# SCH_Electric-Kiln-Controller_EasyEDA.net
KiCad netlist of a schematic drawn in EasyEDA
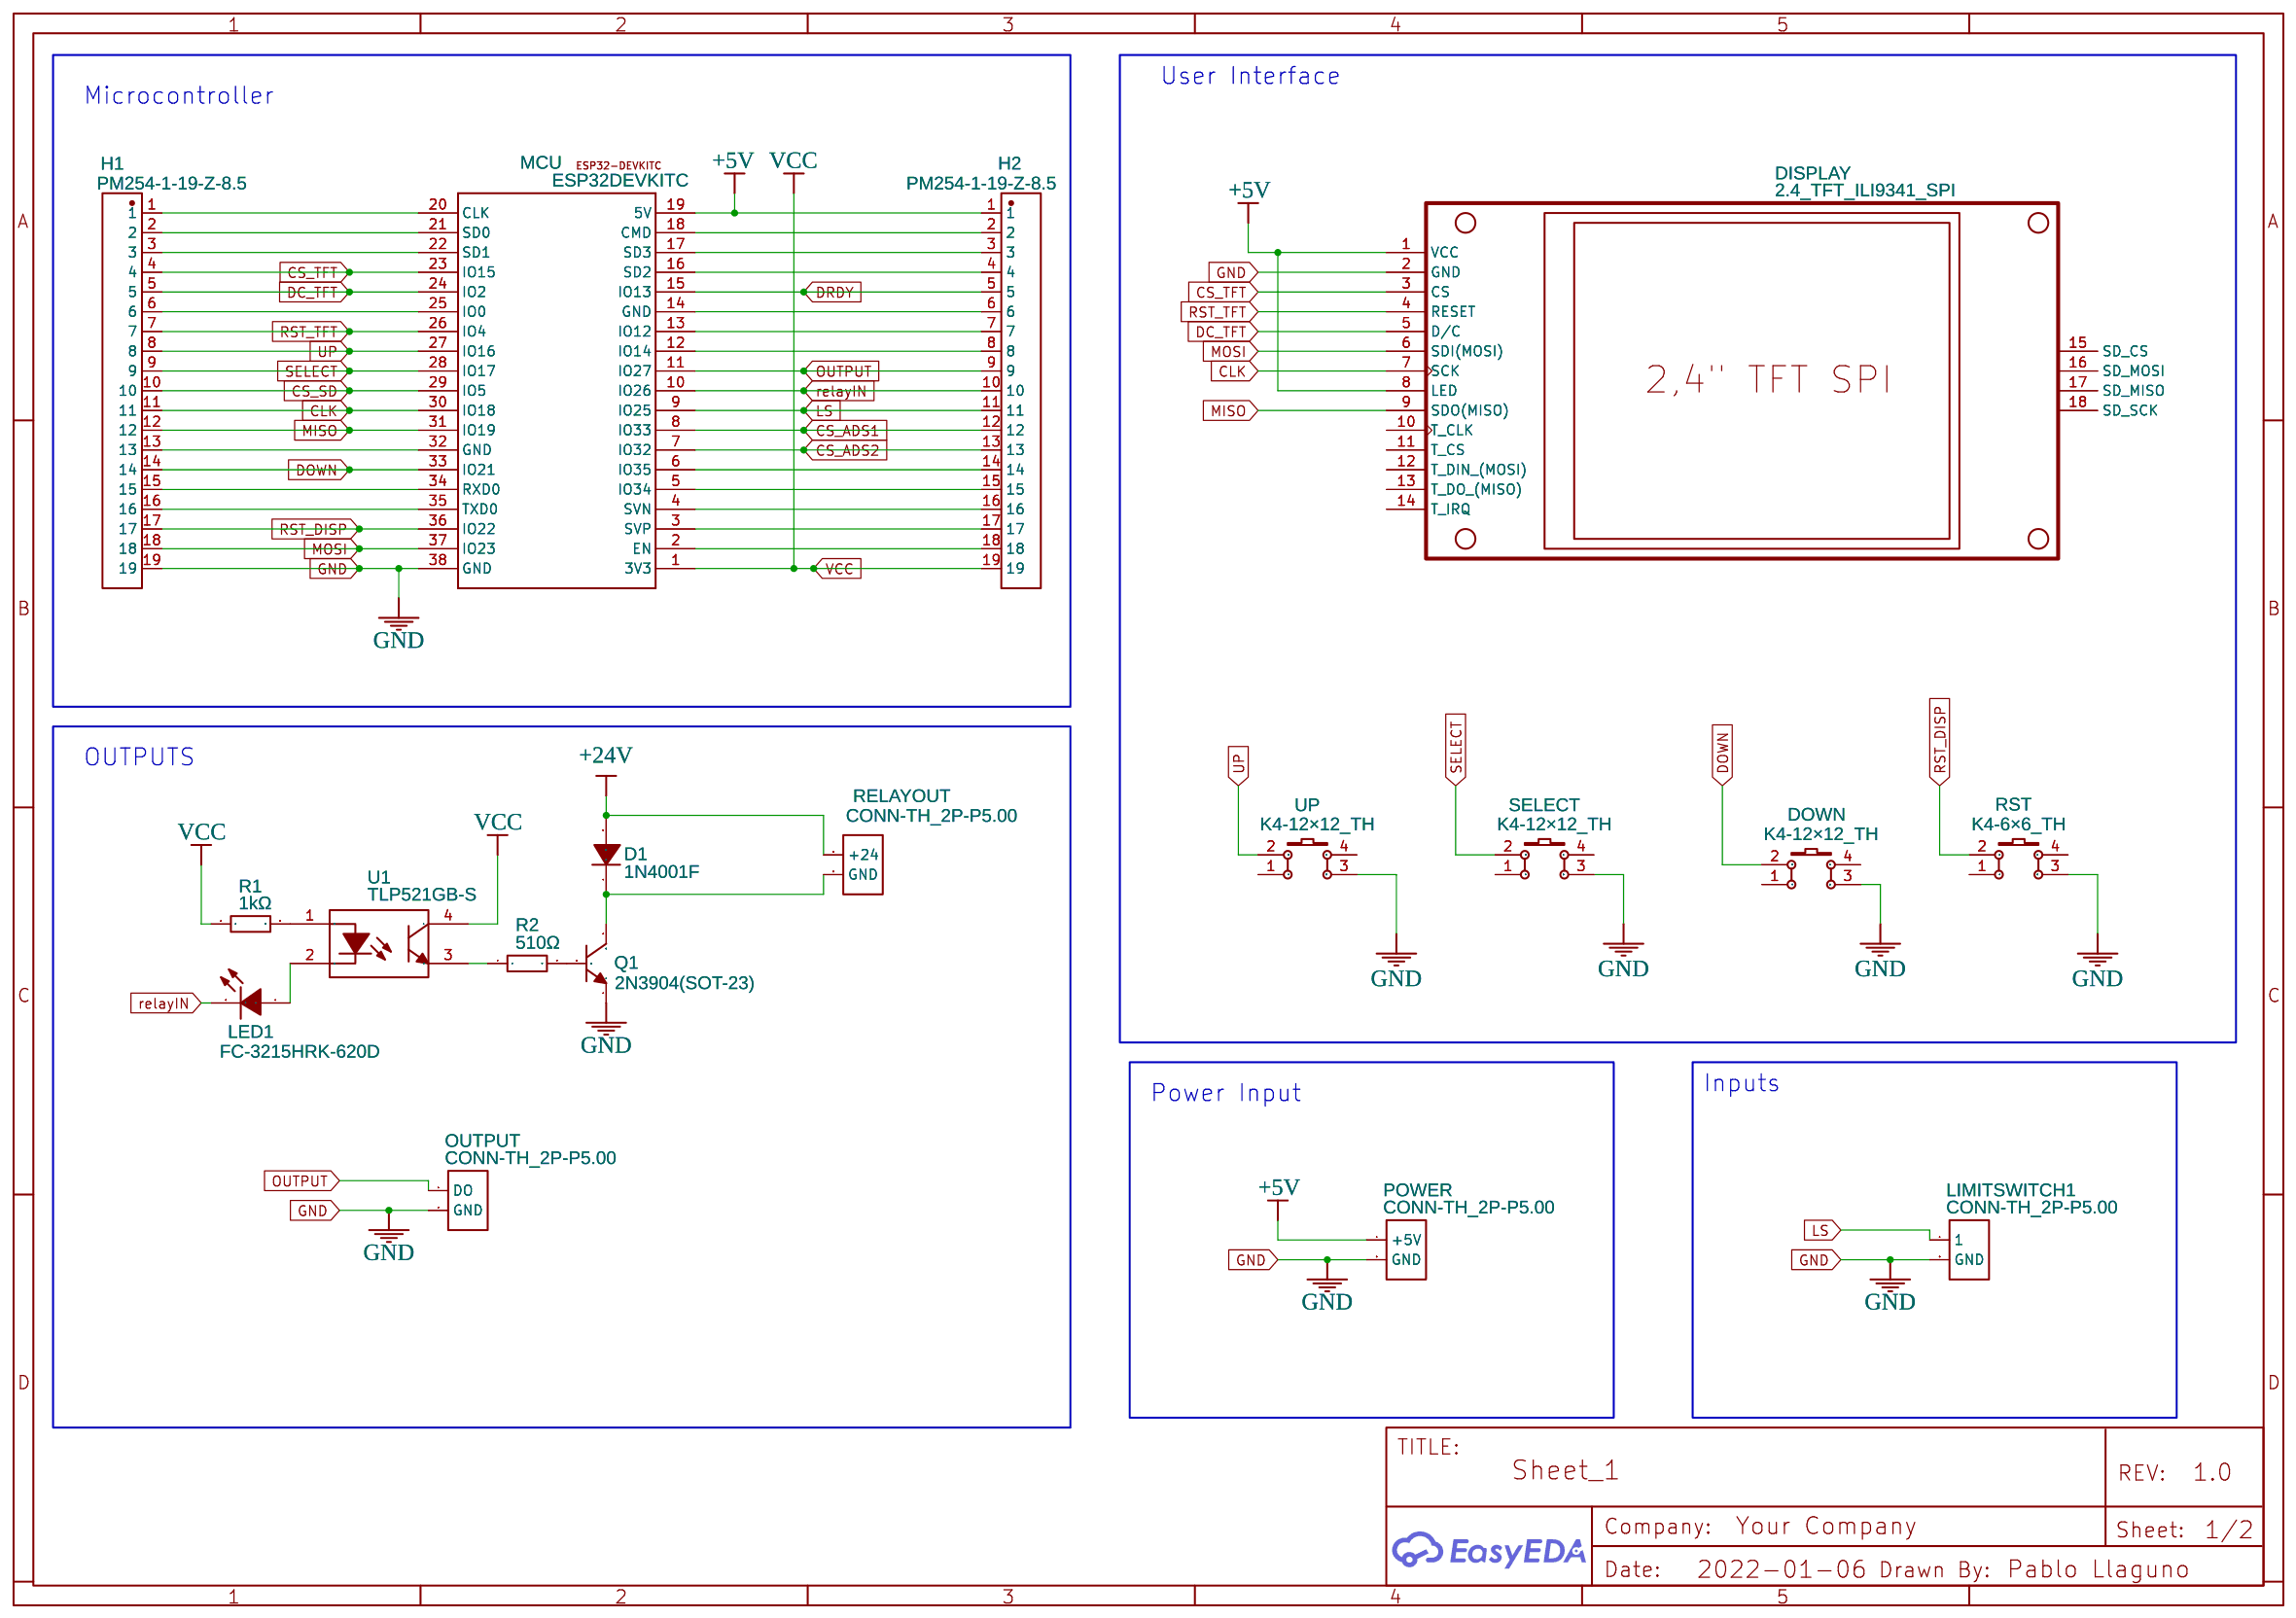
[diagram p0: Sheet_1]
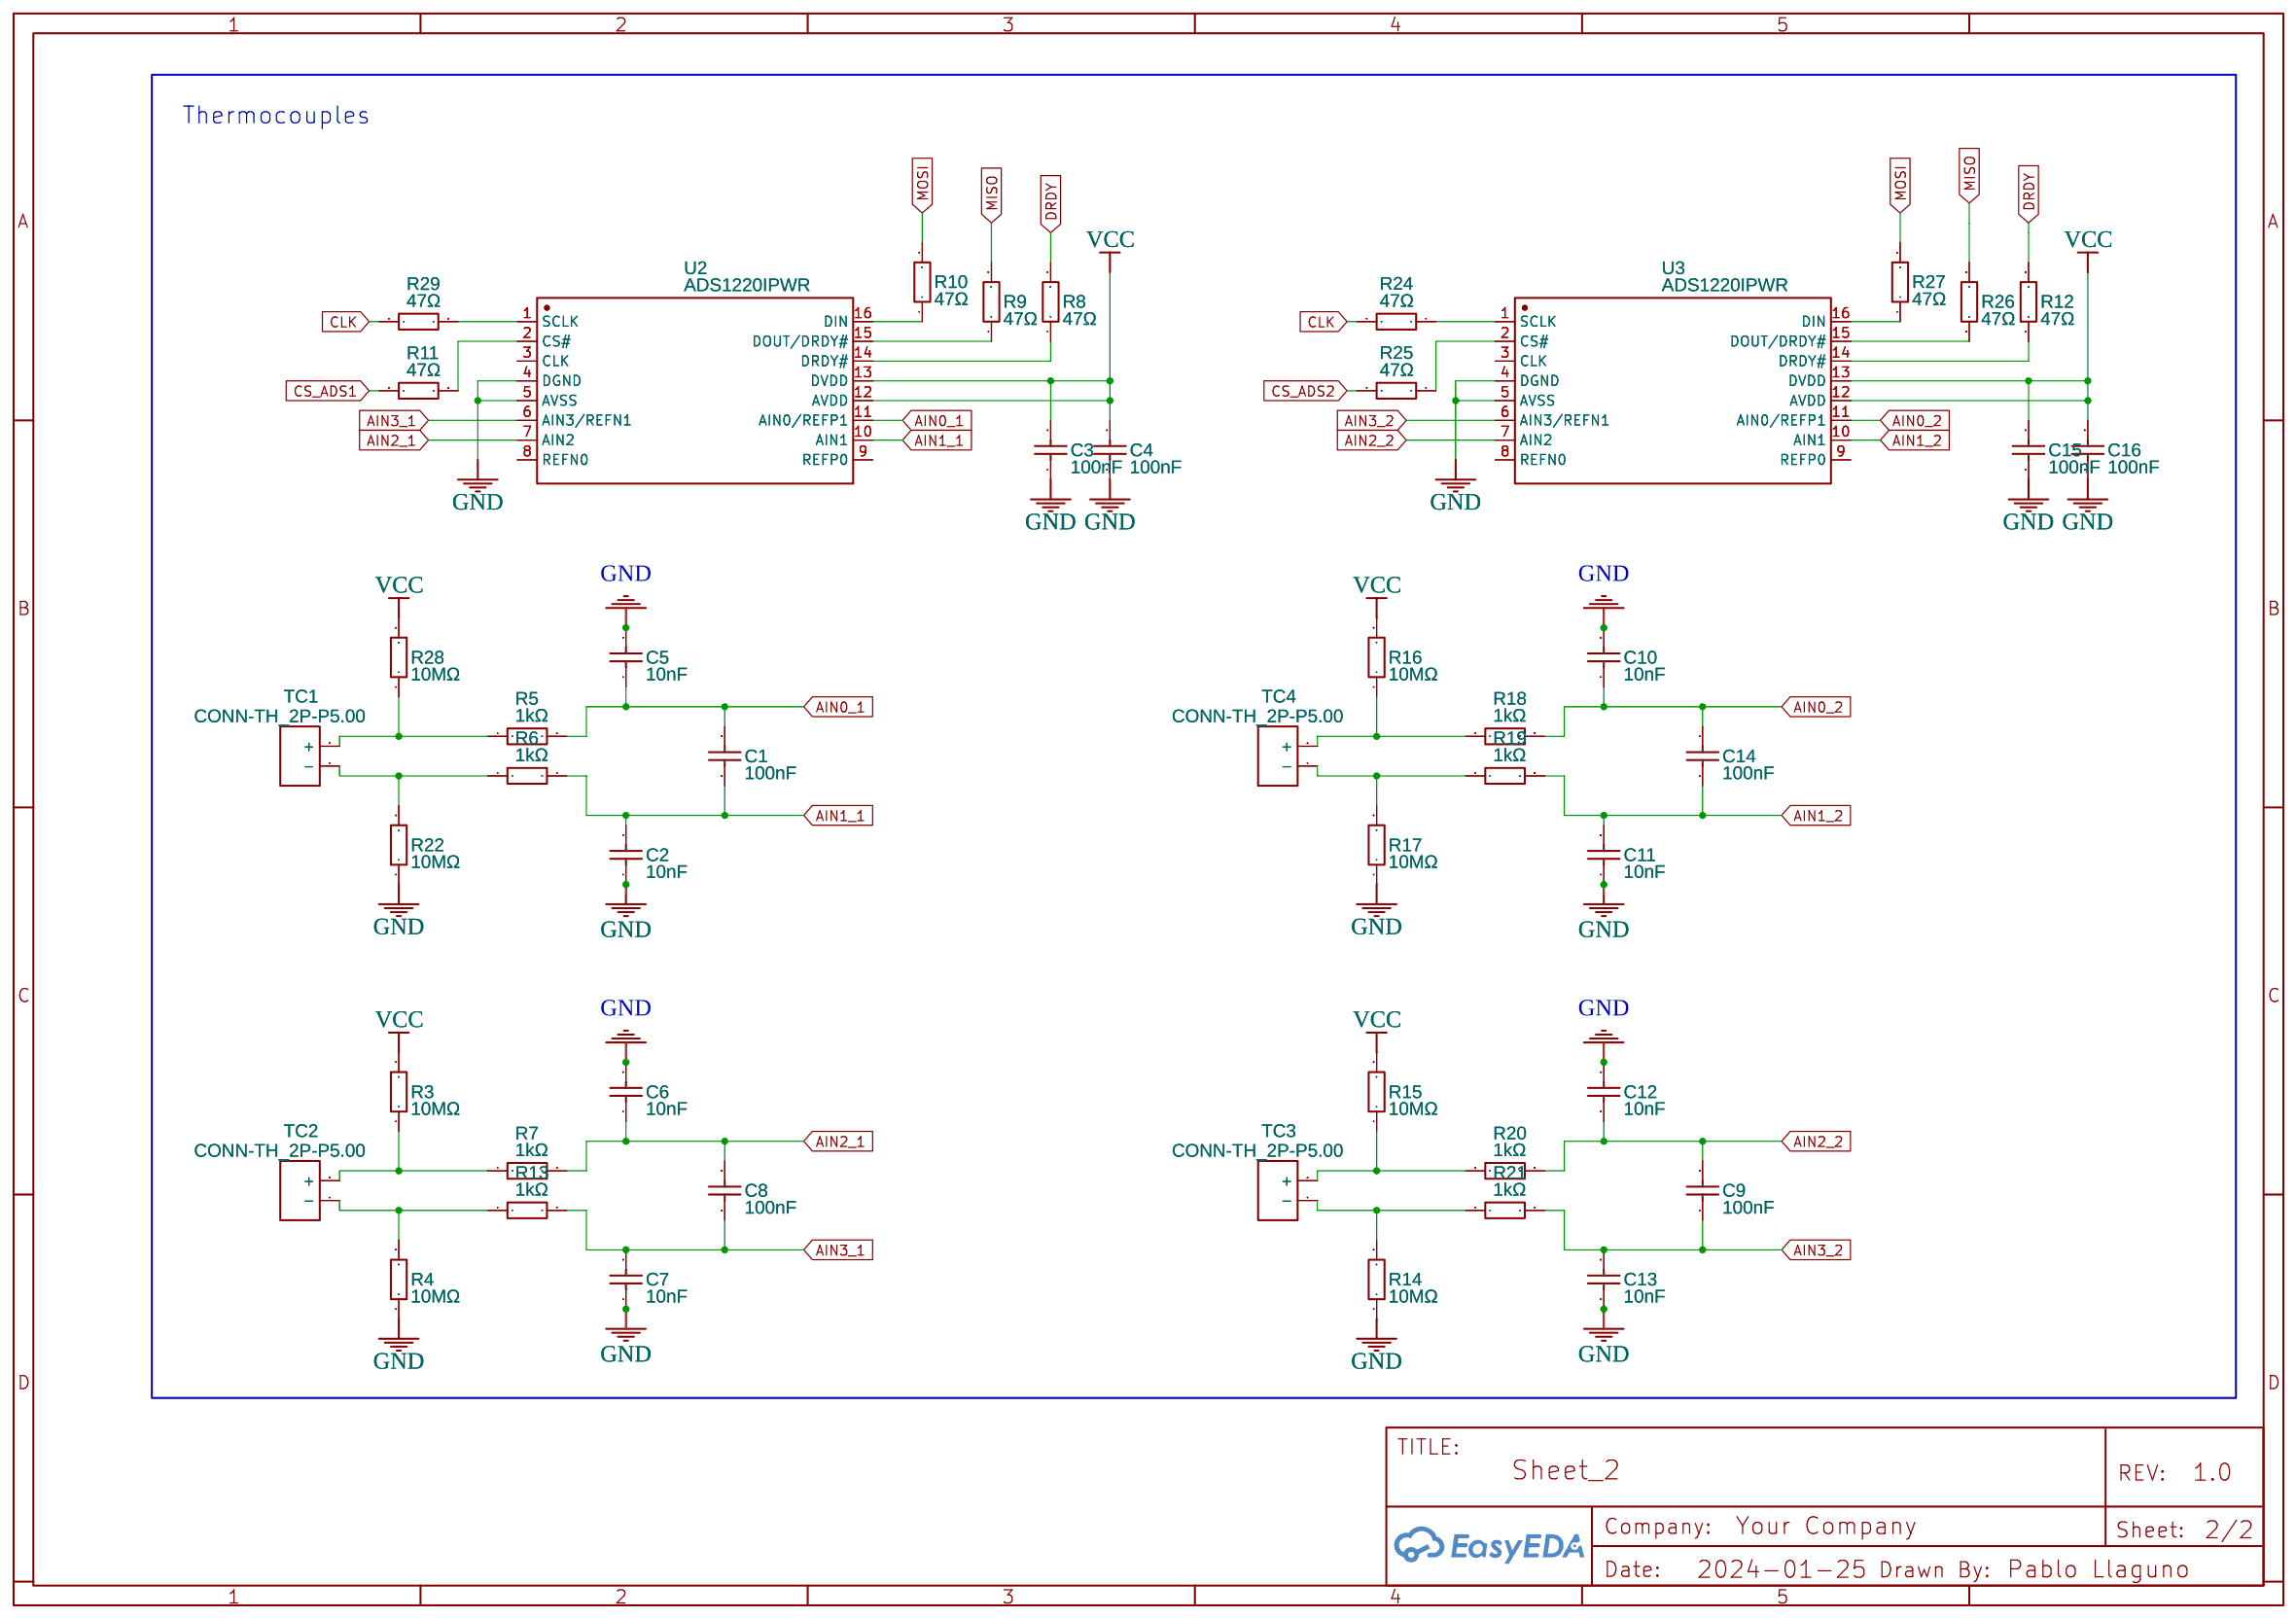
[diagram p1: Sheet_2]

(export (version "E")
  (design (tool "Eeschema 10.0.6"))
  (components
    (comp (ref "D1")
      (value "1N4001F")
      (fields (field (name "Manufacturer") "SHIKUES(时科)"))
      (libsource (lib "") (part "1N4001F"))
    )
    (comp (ref "DISPLAY") (value "2.4_TFT_ILI9341_SPI") (libsource (lib "") (part "2.4_TFT_ILI9341_SPI")))
    (comp (ref "DOWN")
      (value "K4-12×12_TH")
      (fields (field (name "Manufacturer Part") "K2-1103DP-M4SW-04") (field (name "Manufacturer") "韩国韩荣"))
      (libsource (lib "") (part "K4-12×12_TH"))
    )
    (comp (ref "H1")
      (value "PM254-1-19-Z-8.5")
      (fields (field (name "Manufacturer") "HCTL(华灿天禄)"))
      (libsource (lib "") (part "PM254-1-19-Z-8.5_1"))
    )
    (comp (ref "H2")
      (value "PM254-1-19-Z-8.5")
      (fields (field (name "Manufacturer") "HCTL(华灿天禄)"))
      (libsource (lib "") (part "PM254-1-19-Z-8.5"))
    )
    (comp (ref "LED1")
      (value "FC-3215HRK-620D")
      (fields (field (name "Manufacturer Part") "NCD1206R1") (field (name "Manufacturer") "国星光电"))
      (libsource (lib "") (part "FC-3215HRK-620D"))
    )
    (comp (ref "LIMITSWITCH1") (value "CONN-TH_2P-P5.00") (libsource (lib "") (part "CONN-TH_2P-P5.00_2")))
    (comp (ref "MCU") (value "ESP32DEVKITC") (libsource (lib "") (part "ESP32DEVKITC")))
    (comp (ref "OUTPUT") (value "CONN-TH_2P-P5.00") (libsource (lib "") (part "CONN-TH_2P-P5.00_1")))
    (comp (ref "POWER") (value "CONN-TH_2P-P5.00") (libsource (lib "") (part "CONN-TH_2P-P5.00")))
    (comp (ref "Q1")
      (value "2N3904(SOT-23)")
      (fields (field (name "Manufacturer Part") "2n3904S-RTK/PS") (field (name "Manufacturer") "KEC"))
      (libsource (lib "") (part "2N3904(SOT-23)"))
    )
    (comp (ref "R1")
      (value "1kΩ")
      (fields
        (field (name "Manufacturer Part") "0603WAF1001T5E")
        (field (name "Manufacturer") "UNI-ROYAL(厚声)")
      )
      (libsource (lib "") (part "0603WAF1001T5E"))
    )
    (comp (ref "R2")
      (value "510Ω")
      (fields
        (field (name "Manufacturer Part") "0603WAF5100T5E")
        (field (name "Manufacturer") "UNI-ROYAL(厚声)")
      )
      (libsource (lib "") (part "0603WAF5100T5E"))
    )
    (comp (ref "RELAYOUT") (value "CONN-TH_2P-P5.00") (libsource (lib "") (part "CONN-TH_2P-P5.00_3")))
    (comp (ref "RST")
      (value "K4-6×6_TH")
      (fields (field (name "Manufacturer Part") "K2-1102DP-E4SW-04") (field (name "Manufacturer") "韩国韩荣"))
      (libsource (lib "") (part "K4-6×6_TH"))
    )
    (comp (ref "SELECT")
      (value "K4-12×12_TH")
      (fields (field (name "Manufacturer Part") "K2-1103DP-M4SW-04") (field (name "Manufacturer") "韩国韩荣"))
      (libsource (lib "") (part "K4-12×12_TH_1"))
    )
    (comp (ref "U1")
      (value "TLP521GB-S")
      (fields (field (name "Manufacturer") "UMW(广东友台半导体)"))
      (libsource (lib "") (part "TLP521GB-S"))
    )
    (comp (ref "UP")
      (value "K4-12×12_TH")
      (fields (field (name "Manufacturer Part") "K2-1103DP-M4SW-04") (field (name "Manufacturer") "韩国韩荣"))
      (libsource (lib "") (part "K4-12×12_TH_2"))
    )
    (comp (ref "C1")
      (value "100nF")
      (fields
        (field (name "Manufacturer Part") "CL21B104KCFNNNE")
        (field (name "Manufacturer") "SAMSUNG(三星)")
      )
      (libsource (lib "") (part "CL21B104KCFNNNE"))
    )
    (comp (ref "C2")
      (value "10nF")
      (fields
        (field (name "Manufacturer Part") "CL21B103KBANNNC")
        (field (name "Manufacturer") "SAMSUNG(三星)")
      )
      (libsource (lib "") (part "CL21B103KBANNNC"))
    )
    (comp (ref "C3")
      (value "100nF")
      (fields
        (field (name "Manufacturer Part") "CL21B104KCFNNNE")
        (field (name "Manufacturer") "SAMSUNG(三星)")
      )
      (libsource (lib "") (part "CL21B104KCFNNNE"))
    )
    (comp (ref "C4")
      (value "100nF")
      (fields
        (field (name "Manufacturer Part") "CL21B104KCFNNNE")
        (field (name "Manufacturer") "SAMSUNG(三星)")
      )
      (libsource (lib "") (part "CL21B104KCFNNNE"))
    )
    (comp (ref "C5")
      (value "10nF")
      (fields
        (field (name "Manufacturer Part") "CL21B103KBANNNC")
        (field (name "Manufacturer") "SAMSUNG(三星)")
      )
      (libsource (lib "") (part "CL21B103KBANNNC"))
    )
    (comp (ref "C6")
      (value "10nF")
      (fields
        (field (name "Manufacturer Part") "CL21B103KBANNNC")
        (field (name "Manufacturer") "SAMSUNG(三星)")
      )
      (libsource (lib "") (part "CL21B103KBANNNC"))
    )
    (comp (ref "C7")
      (value "10nF")
      (fields
        (field (name "Manufacturer Part") "CL21B103KBANNNC")
        (field (name "Manufacturer") "SAMSUNG(三星)")
      )
      (libsource (lib "") (part "CL21B103KBANNNC"))
    )
    (comp (ref "C8")
      (value "100nF")
      (fields
        (field (name "Manufacturer Part") "CL21B104KCFNNNE")
        (field (name "Manufacturer") "SAMSUNG(三星)")
      )
      (libsource (lib "") (part "CL21B104KCFNNNE"))
    )
    (comp (ref "C9")
      (value "100nF")
      (fields
        (field (name "Manufacturer Part") "CL21B104KCFNNNE")
        (field (name "Manufacturer") "SAMSUNG(三星)")
      )
      (libsource (lib "") (part "CL21B104KCFNNNE"))
    )
    (comp (ref "C10")
      (value "10nF")
      (fields
        (field (name "Manufacturer Part") "CL21B103KBANNNC")
        (field (name "Manufacturer") "SAMSUNG(三星)")
      )
      (libsource (lib "") (part "CL21B103KBANNNC"))
    )
    (comp (ref "C11")
      (value "10nF")
      (fields
        (field (name "Manufacturer Part") "CL21B103KBANNNC")
        (field (name "Manufacturer") "SAMSUNG(三星)")
      )
      (libsource (lib "") (part "CL21B103KBANNNC"))
    )
    (comp (ref "C12")
      (value "10nF")
      (fields
        (field (name "Manufacturer Part") "CL21B103KBANNNC")
        (field (name "Manufacturer") "SAMSUNG(三星)")
      )
      (libsource (lib "") (part "CL21B103KBANNNC"))
    )
    (comp (ref "C13")
      (value "10nF")
      (fields
        (field (name "Manufacturer Part") "CL21B103KBANNNC")
        (field (name "Manufacturer") "SAMSUNG(三星)")
      )
      (libsource (lib "") (part "CL21B103KBANNNC"))
    )
    (comp (ref "C14")
      (value "100nF")
      (fields
        (field (name "Manufacturer Part") "CL21B104KCFNNNE")
        (field (name "Manufacturer") "SAMSUNG(三星)")
      )
      (libsource (lib "") (part "CL21B104KCFNNNE"))
    )
    (comp (ref "C15")
      (value "100nF")
      (fields
        (field (name "Manufacturer Part") "CL21B104KCFNNNE")
        (field (name "Manufacturer") "SAMSUNG(三星)")
      )
      (libsource (lib "") (part "CL21B104KCFNNNE"))
    )
    (comp (ref "C16")
      (value "100nF")
      (fields
        (field (name "Manufacturer Part") "CL21B104KCFNNNE")
        (field (name "Manufacturer") "SAMSUNG(三星)")
      )
      (libsource (lib "") (part "CL21B104KCFNNNE"))
    )
    (comp (ref "R3")
      (value "10MΩ")
      (fields
        (field (name "Manufacturer Part") "0603WAJ0106T5E")
        (field (name "Manufacturer") "UNI-ROYAL(厚声)")
      )
      (libsource (lib "") (part "0603WAJ0106T5E"))
    )
    (comp (ref "R4")
      (value "10MΩ")
      (fields
        (field (name "Manufacturer Part") "0603WAJ0106T5E")
        (field (name "Manufacturer") "UNI-ROYAL(厚声)")
      )
      (libsource (lib "") (part "0603WAJ0106T5E"))
    )
    (comp (ref "R5")
      (value "1kΩ")
      (fields
        (field (name "Manufacturer Part") "0603WAF1001T5E")
        (field (name "Manufacturer") "UNI-ROYAL(厚声)")
      )
      (libsource (lib "") (part "0603WAF1001T5E"))
    )
    (comp (ref "R6")
      (value "1kΩ")
      (fields
        (field (name "Manufacturer Part") "0603WAF1001T5E")
        (field (name "Manufacturer") "UNI-ROYAL(厚声)")
      )
      (libsource (lib "") (part "0603WAF1001T5E"))
    )
    (comp (ref "R7")
      (value "1kΩ")
      (fields
        (field (name "Manufacturer Part") "0603WAF1001T5E")
        (field (name "Manufacturer") "UNI-ROYAL(厚声)")
      )
      (libsource (lib "") (part "0603WAF1001T5E"))
    )
    (comp (ref "R8")
      (value "47Ω")
      (fields
        (field (name "Manufacturer Part") "0603WAJ0470T5E")
        (field (name "Manufacturer") "UNI-ROYAL(厚声)")
      )
      (libsource (lib "") (part "0603WAJ0470T5E_2"))
    )
    (comp (ref "R9")
      (value "47Ω")
      (fields
        (field (name "Manufacturer Part") "0603WAJ0470T5E")
        (field (name "Manufacturer") "UNI-ROYAL(厚声)")
      )
      (libsource (lib "") (part "0603WAJ0470T5E_2"))
    )
    (comp (ref "R10")
      (value "47Ω")
      (fields
        (field (name "Manufacturer Part") "0603WAJ0470T5E")
        (field (name "Manufacturer") "UNI-ROYAL(厚声)")
      )
      (libsource (lib "") (part "0603WAJ0470T5E_2"))
    )
    (comp (ref "R11")
      (value "47Ω")
      (fields
        (field (name "Manufacturer Part") "0603WAJ0470T5E")
        (field (name "Manufacturer") "UNI-ROYAL(厚声)")
      )
      (libsource (lib "") (part "0603WAJ0470T5E"))
    )
    (comp (ref "R12")
      (value "47Ω")
      (fields
        (field (name "Manufacturer Part") "0603WAJ0470T5E")
        (field (name "Manufacturer") "UNI-ROYAL(厚声)")
      )
      (libsource (lib "") (part "0603WAJ0470T5E_2"))
    )
    (comp (ref "R13")
      (value "1kΩ")
      (fields
        (field (name "Manufacturer Part") "0603WAF1001T5E")
        (field (name "Manufacturer") "UNI-ROYAL(厚声)")
      )
      (libsource (lib "") (part "0603WAF1001T5E"))
    )
    (comp (ref "R14")
      (value "10MΩ")
      (fields
        (field (name "Manufacturer Part") "0603WAJ0106T5E")
        (field (name "Manufacturer") "UNI-ROYAL(厚声)")
      )
      (libsource (lib "") (part "0603WAJ0106T5E"))
    )
    (comp (ref "R15")
      (value "10MΩ")
      (fields
        (field (name "Manufacturer Part") "0603WAJ0106T5E")
        (field (name "Manufacturer") "UNI-ROYAL(厚声)")
      )
      (libsource (lib "") (part "0603WAJ0106T5E"))
    )
    (comp (ref "R16")
      (value "10MΩ")
      (fields
        (field (name "Manufacturer Part") "0603WAJ0106T5E")
        (field (name "Manufacturer") "UNI-ROYAL(厚声)")
      )
      (libsource (lib "") (part "0603WAJ0106T5E"))
    )
    (comp (ref "R17")
      (value "10MΩ")
      (fields
        (field (name "Manufacturer Part") "0603WAJ0106T5E")
        (field (name "Manufacturer") "UNI-ROYAL(厚声)")
      )
      (libsource (lib "") (part "0603WAJ0106T5E"))
    )
    (comp (ref "R18")
      (value "1kΩ")
      (fields
        (field (name "Manufacturer Part") "0603WAF1001T5E")
        (field (name "Manufacturer") "UNI-ROYAL(厚声)")
      )
      (libsource (lib "") (part "0603WAF1001T5E"))
    )
    (comp (ref "R19")
      (value "1kΩ")
      (fields
        (field (name "Manufacturer Part") "0603WAF1001T5E")
        (field (name "Manufacturer") "UNI-ROYAL(厚声)")
      )
      (libsource (lib "") (part "0603WAF1001T5E"))
    )
    (comp (ref "R20")
      (value "1kΩ")
      (fields
        (field (name "Manufacturer Part") "0603WAF1001T5E")
        (field (name "Manufacturer") "UNI-ROYAL(厚声)")
      )
      (libsource (lib "") (part "0603WAF1001T5E"))
    )
    (comp (ref "R21")
      (value "1kΩ")
      (fields
        (field (name "Manufacturer Part") "0603WAF1001T5E")
        (field (name "Manufacturer") "UNI-ROYAL(厚声)")
      )
      (libsource (lib "") (part "0603WAF1001T5E"))
    )
    (comp (ref "R22")
      (value "10MΩ")
      (fields
        (field (name "Manufacturer Part") "0603WAJ0106T5E")
        (field (name "Manufacturer") "UNI-ROYAL(厚声)")
      )
      (libsource (lib "") (part "0603WAJ0106T5E"))
    )
    (comp (ref "R24")
      (value "47Ω")
      (fields
        (field (name "Manufacturer Part") "0603WAJ0470T5E")
        (field (name "Manufacturer") "UNI-ROYAL(厚声)")
      )
      (libsource (lib "") (part "0603WAJ0470T5E_1"))
    )
    (comp (ref "R25")
      (value "47Ω")
      (fields
        (field (name "Manufacturer Part") "0603WAJ0470T5E")
        (field (name "Manufacturer") "UNI-ROYAL(厚声)")
      )
      (libsource (lib "") (part "0603WAJ0470T5E_1"))
    )
    (comp (ref "R26")
      (value "47Ω")
      (fields
        (field (name "Manufacturer Part") "0603WAJ0470T5E")
        (field (name "Manufacturer") "UNI-ROYAL(厚声)")
      )
      (libsource (lib "") (part "0603WAJ0470T5E_2"))
    )
    (comp (ref "R27")
      (value "47Ω")
      (fields
        (field (name "Manufacturer Part") "0603WAJ0470T5E")
        (field (name "Manufacturer") "UNI-ROYAL(厚声)")
      )
      (libsource (lib "") (part "0603WAJ0470T5E_2"))
    )
    (comp (ref "R28")
      (value "10MΩ")
      (fields
        (field (name "Manufacturer Part") "0603WAJ0106T5E")
        (field (name "Manufacturer") "UNI-ROYAL(厚声)")
      )
      (libsource (lib "") (part "0603WAJ0106T5E"))
    )
    (comp (ref "R29")
      (value "47Ω")
      (fields
        (field (name "Manufacturer Part") "0603WAJ0470T5E")
        (field (name "Manufacturer") "UNI-ROYAL(厚声)")
      )
      (libsource (lib "") (part "0603WAJ0470T5E"))
    )
    (comp (ref "TC1") (value "CONN-TH_2P-P5.00") (libsource (lib "") (part "CONN-TH_2P-P5.00")))
    (comp (ref "TC2") (value "CONN-TH_2P-P5.00") (libsource (lib "") (part "CONN-TH_2P-P5.00")))
    (comp (ref "TC3") (value "CONN-TH_2P-P5.00") (libsource (lib "") (part "CONN-TH_2P-P5.00")))
    (comp (ref "TC4") (value "CONN-TH_2P-P5.00") (libsource (lib "") (part "CONN-TH_2P-P5.00")))
    (comp (ref "U2")
      (value "ADS1220IPWR")
      (fields (field (name "Manufacturer") "TI(德州仪器)"))
      (libsource (lib "") (part "ADS1220IPWR"))
    )
    (comp (ref "U3")
      (value "ADS1220IPWR")
      (fields (field (name "Manufacturer") "TI(德州仪器)"))
      (libsource (lib "") (part "ADS1220IPWR"))
    )
  )
  (nets
    (net (code "1") (name "+5V") (class "Default")
      (node (ref "DISPLAY") (pin "1") (pinfunction "VCC_1") (pintype "passive"))
      (node (ref "DISPLAY") (pin "8") (pinfunction "LED_8") (pintype "passive"))
      (node (ref "H2") (pin "1") (pinfunction "1_1") (pintype "unspecified"))
      (node (ref "MCU") (pin "19") (pinfunction "5V_19") (pintype "bidirectional"))
      (node (ref "POWER") (pin "1") (pinfunction "+5V_1") (pintype "unspecified"))
    )
    (net (code "2") (name "+24V") (class "Default")
      (node (ref "D1") (pin "2") (pinfunction "A_2") (pintype "unspecified"))
      (node (ref "RELAYOUT") (pin "1") (pinfunction "+24_1") (pintype "unspecified"))
    )
    (net (code "3") (name "AIN0_1") (class "Default")
      (node (ref "C1") (pin "2") (pinfunction "2_2") (pintype "input"))
      (node (ref "C5") (pin "1") (pinfunction "1_1") (pintype "input"))
      (node (ref "R5") (pin "2") (pinfunction "2_2") (pintype "input"))
      (node (ref "U2") (pin "11") (pinfunction "AIN0/REFP1_11") (pintype "unspecified"))
    )
    (net (code "4") (name "AIN0_2") (class "Default")
      (node (ref "C10") (pin "1") (pinfunction "1_1") (pintype "input"))
      (node (ref "C14") (pin "2") (pinfunction "2_2") (pintype "input"))
      (node (ref "R18") (pin "2") (pinfunction "2_2") (pintype "input"))
      (node (ref "U3") (pin "11") (pinfunction "AIN0/REFP1_11") (pintype "unspecified"))
    )
    (net (code "5") (name "AIN1_1") (class "Default")
      (node (ref "C1") (pin "1") (pinfunction "1_1") (pintype "input"))
      (node (ref "C2") (pin "2") (pinfunction "2_2") (pintype "input"))
      (node (ref "R6") (pin "2") (pinfunction "2_2") (pintype "input"))
      (node (ref "U2") (pin "10") (pinfunction "AIN1_10") (pintype "unspecified"))
    )
    (net (code "6") (name "AIN1_2") (class "Default")
      (node (ref "C11") (pin "2") (pinfunction "2_2") (pintype "input"))
      (node (ref "C14") (pin "1") (pinfunction "1_1") (pintype "input"))
      (node (ref "R19") (pin "2") (pinfunction "2_2") (pintype "input"))
      (node (ref "U3") (pin "10") (pinfunction "AIN1_10") (pintype "unspecified"))
    )
    (net (code "7") (name "AIN2_1") (class "Default")
      (node (ref "C6") (pin "1") (pinfunction "1_1") (pintype "input"))
      (node (ref "C8") (pin "2") (pinfunction "2_2") (pintype "input"))
      (node (ref "R7") (pin "2") (pinfunction "2_2") (pintype "input"))
      (node (ref "U2") (pin "7") (pinfunction "AIN2_7") (pintype "unspecified"))
    )
    (net (code "8") (name "AIN2_2") (class "Default")
      (node (ref "C12") (pin "1") (pinfunction "1_1") (pintype "input"))
      (node (ref "C9") (pin "2") (pinfunction "2_2") (pintype "input"))
      (node (ref "R20") (pin "2") (pinfunction "2_2") (pintype "input"))
      (node (ref "U3") (pin "7") (pinfunction "AIN2_7") (pintype "unspecified"))
    )
    (net (code "9") (name "AIN3_1") (class "Default")
      (node (ref "C7") (pin "2") (pinfunction "2_2") (pintype "input"))
      (node (ref "C8") (pin "1") (pinfunction "1_1") (pintype "input"))
      (node (ref "R13") (pin "2") (pinfunction "2_2") (pintype "input"))
      (node (ref "U2") (pin "6") (pinfunction "AIN3/REFN1_6") (pintype "unspecified"))
    )
    (net (code "10") (name "AIN3_2") (class "Default")
      (node (ref "C13") (pin "2") (pinfunction "2_2") (pintype "input"))
      (node (ref "C9") (pin "1") (pinfunction "1_1") (pintype "input"))
      (node (ref "R21") (pin "2") (pinfunction "2_2") (pintype "input"))
      (node (ref "U3") (pin "6") (pinfunction "AIN3/REFN1_6") (pintype "unspecified"))
    )
    (net (code "11") (name "CLK") (class "Default")
      (node (ref "DISPLAY") (pin "7") (pinfunction "SCK_7") (pintype "input"))
      (node (ref "H1") (pin "11") (pinfunction "11_11") (pintype "unspecified"))
      (node (ref "MCU") (pin "30") (pinfunction "IO18_30") (pintype "bidirectional"))
      (node (ref "R24") (pin "2") (pinfunction "2_2") (pintype "input"))
      (node (ref "R29") (pin "1") (pinfunction "1_1") (pintype "input"))
    )
    (net (code "12") (name "CS_ADS1") (class "Default")
      (node (ref "H2") (pin "12") (pinfunction "12_12") (pintype "unspecified"))
      (node (ref "MCU") (pin "8") (pinfunction "IO33_8") (pintype "bidirectional"))
      (node (ref "R11") (pin "1") (pinfunction "1_1") (pintype "input"))
    )
    (net (code "13") (name "CS_ADS2") (class "Default")
      (node (ref "H2") (pin "13") (pinfunction "13_13") (pintype "unspecified"))
      (node (ref "MCU") (pin "7") (pinfunction "IO32_7") (pintype "bidirectional"))
      (node (ref "R25") (pin "2") (pinfunction "2_2") (pintype "input"))
    )
    (net (code "14") (name "CS_SD") (class "Default")
      (node (ref "H1") (pin "10") (pinfunction "10_10") (pintype "unspecified"))
      (node (ref "MCU") (pin "29") (pinfunction "IO5_29") (pintype "bidirectional"))
    )
    (net (code "15") (name "CS_TFT") (class "Default")
      (node (ref "DISPLAY") (pin "3") (pinfunction "CS_3") (pintype "input"))
      (node (ref "H1") (pin "4") (pinfunction "4_4") (pintype "unspecified"))
      (node (ref "MCU") (pin "23") (pinfunction "IO15_23") (pintype "bidirectional"))
    )
    (net (code "16") (name "DC_TFT") (class "Default")
      (node (ref "DISPLAY") (pin "5") (pinfunction "D/C_5") (pintype "input"))
      (node (ref "H1") (pin "5") (pinfunction "5_5") (pintype "unspecified"))
      (node (ref "MCU") (pin "24") (pinfunction "IO2_24") (pintype "bidirectional"))
    )
    (net (code "17") (name "DOWN") (class "Default")
      (node (ref "DOWN") (pin "2") (pinfunction "2_2") (pintype "unspecified"))
      (node (ref "H1") (pin "14") (pinfunction "14_14") (pintype "unspecified"))
      (node (ref "MCU") (pin "33") (pinfunction "IO21_33") (pintype "bidirectional"))
    )
    (net (code "18") (name "DRDY") (class "Default")
      (node (ref "H2") (pin "5") (pinfunction "5_5") (pintype "unspecified"))
      (node (ref "MCU") (pin "15") (pinfunction "IO13_15") (pintype "bidirectional"))
      (node (ref "R12") (pin "2") (pinfunction "2_2") (pintype "input"))
      (node (ref "R8") (pin "2") (pinfunction "2_2") (pintype "input"))
    )
    (net (code "19") (name "GND") (class "Default")
      (node (ref "C10") (pin "2") (pinfunction "2_2") (pintype "input"))
      (node (ref "C11") (pin "1") (pinfunction "1_1") (pintype "input"))
      (node (ref "C12") (pin "2") (pinfunction "2_2") (pintype "input"))
      (node (ref "C13") (pin "1") (pinfunction "1_1") (pintype "input"))
      (node (ref "C15") (pin "1") (pinfunction "1_1") (pintype "input"))
      (node (ref "C16") (pin "1") (pinfunction "1_1") (pintype "input"))
      (node (ref "C2") (pin "1") (pinfunction "1_1") (pintype "input"))
      (node (ref "C3") (pin "1") (pinfunction "1_1") (pintype "input"))
      (node (ref "C4") (pin "1") (pinfunction "1_1") (pintype "input"))
      (node (ref "C5") (pin "2") (pinfunction "2_2") (pintype "input"))
      (node (ref "C6") (pin "2") (pinfunction "2_2") (pintype "input"))
      (node (ref "C7") (pin "1") (pinfunction "1_1") (pintype "input"))
      (node (ref "DISPLAY") (pin "2") (pinfunction "GND_2") (pintype "passive"))
      (node (ref "DOWN") (pin "3") (pinfunction "3_3") (pintype "unspecified"))
      (node (ref "H1") (pin "19") (pinfunction "19_19") (pintype "unspecified"))
      (node (ref "LIMITSWITCH1") (pin "2") (pinfunction "GND_2") (pintype "unspecified"))
      (node (ref "MCU") (pin "38") (pinfunction "GND_38") (pintype "bidirectional"))
      (node (ref "OUTPUT") (pin "2") (pinfunction "GND_2") (pintype "unspecified"))
      (node (ref "POWER") (pin "2") (pinfunction "GND_2") (pintype "unspecified"))
      (node (ref "Q1") (pin "1") (pinfunction "E_1") (pintype "input"))
      (node (ref "R14") (pin "1") (pinfunction "1_1") (pintype "input"))
      (node (ref "R17") (pin "1") (pinfunction "1_1") (pintype "input"))
      (node (ref "R22") (pin "1") (pinfunction "1_1") (pintype "input"))
      (node (ref "R4") (pin "1") (pinfunction "1_1") (pintype "input"))
      (node (ref "RST") (pin "3") (pinfunction "3_3") (pintype "unspecified"))
      (node (ref "SELECT") (pin "3") (pinfunction "3_3") (pintype "unspecified"))
      (node (ref "U2") (pin "4") (pinfunction "DGND_4") (pintype "unspecified"))
      (node (ref "U2") (pin "5") (pinfunction "AVSS_5") (pintype "unspecified"))
      (node (ref "U3") (pin "4") (pinfunction "DGND_4") (pintype "unspecified"))
      (node (ref "U3") (pin "5") (pinfunction "AVSS_5") (pintype "unspecified"))
      (node (ref "UP") (pin "3") (pinfunction "3_3") (pintype "unspecified"))
    )
    (net (code "20") (name "LS") (class "Default")
      (node (ref "H2") (pin "11") (pinfunction "11_11") (pintype "unspecified"))
      (node (ref "LIMITSWITCH1") (pin "1") (pinfunction "1_1") (pintype "unspecified"))
      (node (ref "MCU") (pin "9") (pinfunction "IO25_9") (pintype "bidirectional"))
    )
    (net (code "21") (name "MISO") (class "Default")
      (node (ref "DISPLAY") (pin "9") (pinfunction "SDO(MISO)_9") (pintype "output"))
      (node (ref "H1") (pin "12") (pinfunction "12_12") (pintype "unspecified"))
      (node (ref "MCU") (pin "31") (pinfunction "IO19_31") (pintype "bidirectional"))
      (node (ref "R26") (pin "2") (pinfunction "2_2") (pintype "input"))
      (node (ref "R9") (pin "2") (pinfunction "2_2") (pintype "input"))
    )
    (net (code "22") (name "MOSI") (class "Default")
      (node (ref "DISPLAY") (pin "6") (pinfunction "SDI(MOSI)_6") (pintype "input"))
      (node (ref "H1") (pin "18") (pinfunction "18_18") (pintype "unspecified"))
      (node (ref "MCU") (pin "37") (pinfunction "IO23_37") (pintype "bidirectional"))
      (node (ref "R10") (pin "2") (pinfunction "2_2") (pintype "input"))
      (node (ref "R27") (pin "2") (pinfunction "2_2") (pintype "input"))
    )
    (net (code "23") (name "Net-(D1-C)") (class "Default")
      (node (ref "D1") (pin "1") (pinfunction "C_1") (pintype "unspecified"))
      (node (ref "Q1") (pin "3") (pinfunction "C_3") (pintype "input"))
      (node (ref "RELAYOUT") (pin "2") (pinfunction "GND_2") (pintype "unspecified"))
    )
    (net (code "24") (name "Net-(H1-Pad13)") (class "Default")
      (node (ref "H1") (pin "13") (pinfunction "13_13") (pintype "unspecified"))
      (node (ref "MCU") (pin "32") (pinfunction "GND_32") (pintype "bidirectional"))
    )
    (net (code "25") (name "Net-(H2-Pad6)") (class "Default")
      (node (ref "H2") (pin "6") (pinfunction "6_6") (pintype "unspecified"))
      (node (ref "MCU") (pin "14") (pinfunction "GND_14") (pintype "bidirectional"))
    )
    (net (code "26") (name "Net-(LED1-A)") (class "Default")
      (node (ref "LED1") (pin "1") (pinfunction "A_1") (pintype "unspecified"))
      (node (ref "U1") (pin "2") (pinfunction "2_2") (pintype "unspecified"))
    )
    (net (code "27") (name "Net-(MCU-CLK)") (class "Default")
      (node (ref "H1") (pin "1") (pinfunction "1_1") (pintype "unspecified"))
      (node (ref "MCU") (pin "20") (pinfunction "CLK_20") (pintype "bidirectional"))
    )
    (net (code "28") (name "Net-(MCU-CMD)") (class "Default")
      (node (ref "H2") (pin "2") (pinfunction "2_2") (pintype "unspecified"))
      (node (ref "MCU") (pin "18") (pinfunction "CMD_18") (pintype "bidirectional"))
    )
    (net (code "29") (name "Net-(MCU-EN)") (class "Default")
      (node (ref "H2") (pin "18") (pinfunction "18_18") (pintype "unspecified"))
      (node (ref "MCU") (pin "2") (pinfunction "EN_2") (pintype "bidirectional"))
    )
    (net (code "30") (name "Net-(MCU-IO0)") (class "Default")
      (node (ref "H1") (pin "6") (pinfunction "6_6") (pintype "unspecified"))
      (node (ref "MCU") (pin "25") (pinfunction "IO0_25") (pintype "bidirectional"))
    )
    (net (code "31") (name "Net-(MCU-IO12)") (class "Default")
      (node (ref "H2") (pin "7") (pinfunction "7_7") (pintype "unspecified"))
      (node (ref "MCU") (pin "13") (pinfunction "IO12_13") (pintype "bidirectional"))
    )
    (net (code "32") (name "Net-(MCU-IO14)") (class "Default")
      (node (ref "H2") (pin "8") (pinfunction "8_8") (pintype "unspecified"))
      (node (ref "MCU") (pin "12") (pinfunction "IO14_12") (pintype "bidirectional"))
    )
    (net (code "33") (name "Net-(MCU-IO34)") (class "Default")
      (node (ref "H2") (pin "15") (pinfunction "15_15") (pintype "unspecified"))
      (node (ref "MCU") (pin "5") (pinfunction "IO34_5") (pintype "bidirectional"))
    )
    (net (code "34") (name "Net-(MCU-IO35)") (class "Default")
      (node (ref "H2") (pin "14") (pinfunction "14_14") (pintype "unspecified"))
      (node (ref "MCU") (pin "6") (pinfunction "IO35_6") (pintype "bidirectional"))
    )
    (net (code "35") (name "Net-(MCU-RXD0)") (class "Default")
      (node (ref "H1") (pin "15") (pinfunction "15_15") (pintype "unspecified"))
      (node (ref "MCU") (pin "34") (pinfunction "RXD0_34") (pintype "bidirectional"))
    )
    (net (code "36") (name "Net-(MCU-SD0)") (class "Default")
      (node (ref "H1") (pin "2") (pinfunction "2_2") (pintype "unspecified"))
      (node (ref "MCU") (pin "21") (pinfunction "SD0_21") (pintype "bidirectional"))
    )
    (net (code "37") (name "Net-(MCU-SD1)") (class "Default")
      (node (ref "H1") (pin "3") (pinfunction "3_3") (pintype "unspecified"))
      (node (ref "MCU") (pin "22") (pinfunction "SD1_22") (pintype "bidirectional"))
    )
    (net (code "38") (name "Net-(MCU-SD2)") (class "Default")
      (node (ref "H2") (pin "4") (pinfunction "4_4") (pintype "unspecified"))
      (node (ref "MCU") (pin "16") (pinfunction "SD2_16") (pintype "bidirectional"))
    )
    (net (code "39") (name "Net-(MCU-SD3)") (class "Default")
      (node (ref "H2") (pin "3") (pinfunction "3_3") (pintype "unspecified"))
      (node (ref "MCU") (pin "17") (pinfunction "SD3_17") (pintype "bidirectional"))
    )
    (net (code "40") (name "Net-(MCU-SVN)") (class "Default")
      (node (ref "H2") (pin "16") (pinfunction "16_16") (pintype "unspecified"))
      (node (ref "MCU") (pin "4") (pinfunction "SVN_4") (pintype "bidirectional"))
    )
    (net (code "41") (name "Net-(MCU-SVP)") (class "Default")
      (node (ref "H2") (pin "17") (pinfunction "17_17") (pintype "unspecified"))
      (node (ref "MCU") (pin "3") (pinfunction "SVP_3") (pintype "bidirectional"))
    )
    (net (code "42") (name "Net-(MCU-TXD0)") (class "Default")
      (node (ref "H1") (pin "16") (pinfunction "16_16") (pintype "unspecified"))
      (node (ref "MCU") (pin "35") (pinfunction "TXD0_35") (pintype "bidirectional"))
    )
    (net (code "43") (name "Net-(Q1-B)") (class "Default")
      (node (ref "Q1") (pin "2") (pinfunction "B_2") (pintype "input"))
      (node (ref "R2") (pin "2") (pinfunction "2_2") (pintype "input"))
    )
    (net (code "44") (name "Net-(R1-Pad2)") (class "Default")
      (node (ref "R1") (pin "2") (pinfunction "2_2") (pintype "input"))
      (node (ref "U1") (pin "1") (pinfunction "1_1") (pintype "unspecified"))
    )
    (net (code "45") (name "Net-(R2-Pad1)") (class "Default")
      (node (ref "R2") (pin "1") (pinfunction "1_1") (pintype "input"))
      (node (ref "U1") (pin "3") (pinfunction "3_3") (pintype "unspecified"))
    )
    (net (code "46") (name "Net-(TC1-+)") (class "Default")
      (node (ref "R28") (pin "1") (pinfunction "1_1") (pintype "input"))
      (node (ref "R5") (pin "1") (pinfunction "1_1") (pintype "input"))
      (node (ref "TC1") (pin "2") (pinfunction "+_2") (pintype "unspecified"))
    )
    (net (code "47") (name "Net-(TC1--)") (class "Default")
      (node (ref "R22") (pin "2") (pinfunction "2_2") (pintype "input"))
      (node (ref "R6") (pin "1") (pinfunction "1_1") (pintype "input"))
      (node (ref "TC1") (pin "1") (pinfunction "-_1") (pintype "unspecified"))
    )
    (net (code "48") (name "Net-(TC2-+)") (class "Default")
      (node (ref "R3") (pin "1") (pinfunction "1_1") (pintype "input"))
      (node (ref "R7") (pin "1") (pinfunction "1_1") (pintype "input"))
      (node (ref "TC2") (pin "2") (pinfunction "+_2") (pintype "unspecified"))
    )
    (net (code "49") (name "Net-(TC2--)") (class "Default")
      (node (ref "R13") (pin "1") (pinfunction "1_1") (pintype "input"))
      (node (ref "R4") (pin "2") (pinfunction "2_2") (pintype "input"))
      (node (ref "TC2") (pin "1") (pinfunction "-_1") (pintype "unspecified"))
    )
    (net (code "50") (name "Net-(TC3-+)") (class "Default")
      (node (ref "R15") (pin "1") (pinfunction "1_1") (pintype "input"))
      (node (ref "R20") (pin "1") (pinfunction "1_1") (pintype "input"))
      (node (ref "TC3") (pin "2") (pinfunction "+_2") (pintype "unspecified"))
    )
    (net (code "51") (name "Net-(TC3--)") (class "Default")
      (node (ref "R14") (pin "2") (pinfunction "2_2") (pintype "input"))
      (node (ref "R21") (pin "1") (pinfunction "1_1") (pintype "input"))
      (node (ref "TC3") (pin "1") (pinfunction "-_1") (pintype "unspecified"))
    )
    (net (code "52") (name "Net-(TC4-+)") (class "Default")
      (node (ref "R16") (pin "1") (pinfunction "1_1") (pintype "input"))
      (node (ref "R18") (pin "1") (pinfunction "1_1") (pintype "input"))
      (node (ref "TC4") (pin "2") (pinfunction "+_2") (pintype "unspecified"))
    )
    (net (code "53") (name "Net-(TC4--)") (class "Default")
      (node (ref "R17") (pin "2") (pinfunction "2_2") (pintype "input"))
      (node (ref "R19") (pin "1") (pinfunction "1_1") (pintype "input"))
      (node (ref "TC4") (pin "1") (pinfunction "-_1") (pintype "unspecified"))
    )
    (net (code "54") (name "Net-(U2-CS#)") (class "Default")
      (node (ref "R11") (pin "2") (pinfunction "2_2") (pintype "input"))
      (node (ref "U2") (pin "2") (pinfunction "CS#_2") (pintype "unspecified"))
    )
    (net (code "55") (name "Net-(U2-DIN)") (class "Default")
      (node (ref "R10") (pin "1") (pinfunction "1_1") (pintype "input"))
      (node (ref "U2") (pin "16") (pinfunction "DIN_16") (pintype "unspecified"))
    )
    (net (code "56") (name "Net-(U2-DOUT{slash}DRDY#)") (class "Default")
      (node (ref "R9") (pin "1") (pinfunction "1_1") (pintype "input"))
      (node (ref "U2") (pin "15") (pinfunction "DOUT/DRDY#_15") (pintype "unspecified"))
    )
    (net (code "57") (name "Net-(U2-DRDY#)") (class "Default")
      (node (ref "R8") (pin "1") (pinfunction "1_1") (pintype "input"))
      (node (ref "U2") (pin "14") (pinfunction "DRDY#_14") (pintype "unspecified"))
    )
    (net (code "58") (name "Net-(U2-SCLK)") (class "Default")
      (node (ref "R29") (pin "2") (pinfunction "2_2") (pintype "input"))
      (node (ref "U2") (pin "1") (pinfunction "SCLK_1") (pintype "unspecified"))
    )
    (net (code "59") (name "Net-(U3-CS#)") (class "Default")
      (node (ref "R25") (pin "1") (pinfunction "1_1") (pintype "input"))
      (node (ref "U3") (pin "2") (pinfunction "CS#_2") (pintype "unspecified"))
    )
    (net (code "60") (name "Net-(U3-DIN)") (class "Default")
      (node (ref "R27") (pin "1") (pinfunction "1_1") (pintype "input"))
      (node (ref "U3") (pin "16") (pinfunction "DIN_16") (pintype "unspecified"))
    )
    (net (code "61") (name "Net-(U3-DOUT{slash}DRDY#)") (class "Default")
      (node (ref "R26") (pin "1") (pinfunction "1_1") (pintype "input"))
      (node (ref "U3") (pin "15") (pinfunction "DOUT/DRDY#_15") (pintype "unspecified"))
    )
    (net (code "62") (name "Net-(U3-DRDY#)") (class "Default")
      (node (ref "R12") (pin "1") (pinfunction "1_1") (pintype "input"))
      (node (ref "U3") (pin "14") (pinfunction "DRDY#_14") (pintype "unspecified"))
    )
    (net (code "63") (name "Net-(U3-SCLK)") (class "Default")
      (node (ref "R24") (pin "1") (pinfunction "1_1") (pintype "input"))
      (node (ref "U3") (pin "1") (pinfunction "SCLK_1") (pintype "unspecified"))
    )
    (net (code "64") (name "OUTPUT") (class "Default")
      (node (ref "H2") (pin "9") (pinfunction "9_9") (pintype "unspecified"))
      (node (ref "MCU") (pin "11") (pinfunction "IO27_11") (pintype "bidirectional"))
      (node (ref "OUTPUT") (pin "1") (pinfunction "DO_1") (pintype "unspecified"))
    )
    (net (code "65") (name "RST_DISP") (class "Default")
      (node (ref "H1") (pin "17") (pinfunction "17_17") (pintype "unspecified"))
      (node (ref "MCU") (pin "36") (pinfunction "IO22_36") (pintype "bidirectional"))
      (node (ref "RST") (pin "2") (pinfunction "2_2") (pintype "unspecified"))
    )
    (net (code "66") (name "RST_TFT") (class "Default")
      (node (ref "DISPLAY") (pin "4") (pinfunction "RESET_4") (pintype "input"))
      (node (ref "H1") (pin "7") (pinfunction "7_7") (pintype "unspecified"))
      (node (ref "MCU") (pin "26") (pinfunction "IO4_26") (pintype "bidirectional"))
    )
    (net (code "67") (name "SELECT") (class "Default")
      (node (ref "H1") (pin "9") (pinfunction "9_9") (pintype "unspecified"))
      (node (ref "MCU") (pin "28") (pinfunction "IO17_28") (pintype "bidirectional"))
      (node (ref "SELECT") (pin "2") (pinfunction "2_2") (pintype "unspecified"))
    )
    (net (code "68") (name "UP") (class "Default")
      (node (ref "H1") (pin "8") (pinfunction "8_8") (pintype "unspecified"))
      (node (ref "MCU") (pin "27") (pinfunction "IO16_27") (pintype "bidirectional"))
      (node (ref "UP") (pin "2") (pinfunction "2_2") (pintype "unspecified"))
    )
    (net (code "69") (name "VCC") (class "Default")
      (node (ref "C15") (pin "2") (pinfunction "2_2") (pintype "input"))
      (node (ref "C16") (pin "2") (pinfunction "2_2") (pintype "input"))
      (node (ref "C3") (pin "2") (pinfunction "2_2") (pintype "input"))
      (node (ref "C4") (pin "2") (pinfunction "2_2") (pintype "input"))
      (node (ref "H2") (pin "19") (pinfunction "19_19") (pintype "unspecified"))
      (node (ref "MCU") (pin "1") (pinfunction "3V3_1") (pintype "bidirectional"))
      (node (ref "R1") (pin "1") (pinfunction "1_1") (pintype "input"))
      (node (ref "R15") (pin "2") (pinfunction "2_2") (pintype "input"))
      (node (ref "R16") (pin "2") (pinfunction "2_2") (pintype "input"))
      (node (ref "R28") (pin "2") (pinfunction "2_2") (pintype "input"))
      (node (ref "R3") (pin "2") (pinfunction "2_2") (pintype "input"))
      (node (ref "U1") (pin "4") (pinfunction "4_4") (pintype "unspecified"))
      (node (ref "U2") (pin "12") (pinfunction "AVDD_12") (pintype "unspecified"))
      (node (ref "U2") (pin "13") (pinfunction "DVDD_13") (pintype "unspecified"))
      (node (ref "U3") (pin "12") (pinfunction "AVDD_12") (pintype "unspecified"))
      (node (ref "U3") (pin "13") (pinfunction "DVDD_13") (pintype "unspecified"))
    )
    (net (code "70") (name "relayIN") (class "Default")
      (node (ref "H2") (pin "10") (pinfunction "10_10") (pintype "unspecified"))
      (node (ref "LED1") (pin "2") (pinfunction "K_2") (pintype "unspecified"))
      (node (ref "MCU") (pin "10") (pinfunction "IO26_10") (pintype "bidirectional"))
    )
    (net (code "71") (name "unconnected-(DISPLAY-SD_CS-Pad15)") (class "Default")
      (node (ref "DISPLAY") (pin "15") (pinfunction "SD_CS_15") (pintype "unspecified"))
    )
    (net (code "72") (name "unconnected-(DISPLAY-SD_MISO-Pad17)") (class "Default")
      (node (ref "DISPLAY") (pin "17") (pinfunction "SD_MISO_17") (pintype "unspecified"))
    )
    (net (code "73") (name "unconnected-(DISPLAY-SD_MOSI-Pad16)") (class "Default")
      (node (ref "DISPLAY") (pin "16") (pinfunction "SD_MOSI_16") (pintype "unspecified"))
    )
    (net (code "74") (name "unconnected-(DISPLAY-SD_SCK-Pad18)") (class "Default")
      (node (ref "DISPLAY") (pin "18") (pinfunction "SD_SCK_18") (pintype "unspecified"))
    )
    (net (code "75") (name "unconnected-(DISPLAY-T_CLK-Pad10)") (class "Default")
      (node (ref "DISPLAY") (pin "10") (pinfunction "T_CLK_10") (pintype "input"))
    )
    (net (code "76") (name "unconnected-(DISPLAY-T_CS-Pad11)") (class "Default")
      (node (ref "DISPLAY") (pin "11") (pinfunction "T_CS_11") (pintype "input"))
    )
    (net (code "77") (name "unconnected-(DISPLAY-T_DIN_(MOSI)-Pad12)") (class "Default")
      (node (ref "DISPLAY") (pin "12") (pinfunction "T_DIN_(MOSI)_12") (pintype "input"))
    )
    (net (code "78") (name "unconnected-(DISPLAY-T_DO_(MISO)-Pad13)") (class "Default")
      (node (ref "DISPLAY") (pin "13") (pinfunction "T_DO_(MISO)_13") (pintype "output"))
    )
    (net (code "79") (name "unconnected-(DISPLAY-T_IRQ-Pad14)") (class "Default")
      (node (ref "DISPLAY") (pin "14") (pinfunction "T_IRQ_14") (pintype "output"))
    )
    (net (code "80") (name "unconnected-(DOWN-Pad1)") (class "Default")
      (node (ref "DOWN") (pin "1") (pinfunction "1_1") (pintype "unspecified"))
    )
    (net (code "81") (name "unconnected-(DOWN-Pad4)") (class "Default")
      (node (ref "DOWN") (pin "4") (pinfunction "4_4") (pintype "unspecified"))
    )
    (net (code "82") (name "unconnected-(RST-Pad1)") (class "Default")
      (node (ref "RST") (pin "1") (pinfunction "1_1") (pintype "unspecified"))
    )
    (net (code "83") (name "unconnected-(RST-Pad4)") (class "Default")
      (node (ref "RST") (pin "4") (pinfunction "4_4") (pintype "unspecified"))
    )
    (net (code "84") (name "unconnected-(SELECT-Pad1)") (class "Default")
      (node (ref "SELECT") (pin "1") (pinfunction "1_1") (pintype "unspecified"))
    )
    (net (code "85") (name "unconnected-(SELECT-Pad4)") (class "Default")
      (node (ref "SELECT") (pin "4") (pinfunction "4_4") (pintype "unspecified"))
    )
    (net (code "86") (name "unconnected-(U2-CLK-Pad3)") (class "Default")
      (node (ref "U2") (pin "3") (pinfunction "CLK_3") (pintype "unspecified"))
    )
    (net (code "87") (name "unconnected-(U2-REFN0-Pad8)") (class "Default")
      (node (ref "U2") (pin "8") (pinfunction "REFN0_8") (pintype "unspecified"))
    )
    (net (code "88") (name "unconnected-(U2-REFP0-Pad9)") (class "Default")
      (node (ref "U2") (pin "9") (pinfunction "REFP0_9") (pintype "unspecified"))
    )
    (net (code "89") (name "unconnected-(U3-CLK-Pad3)") (class "Default")
      (node (ref "U3") (pin "3") (pinfunction "CLK_3") (pintype "unspecified"))
    )
    (net (code "90") (name "unconnected-(U3-REFN0-Pad8)") (class "Default")
      (node (ref "U3") (pin "8") (pinfunction "REFN0_8") (pintype "unspecified"))
    )
    (net (code "91") (name "unconnected-(U3-REFP0-Pad9)") (class "Default")
      (node (ref "U3") (pin "9") (pinfunction "REFP0_9") (pintype "unspecified"))
    )
    (net (code "92") (name "unconnected-(UP-Pad1)") (class "Default")
      (node (ref "UP") (pin "1") (pinfunction "1_1") (pintype "unspecified"))
    )
    (net (code "93") (name "unconnected-(UP-Pad4)") (class "Default")
      (node (ref "UP") (pin "4") (pinfunction "4_4") (pintype "unspecified"))
    )
  )
)
